# MCP1726_PINOUT.net
KiCad netlist of a schematic drawn in Altium Designer
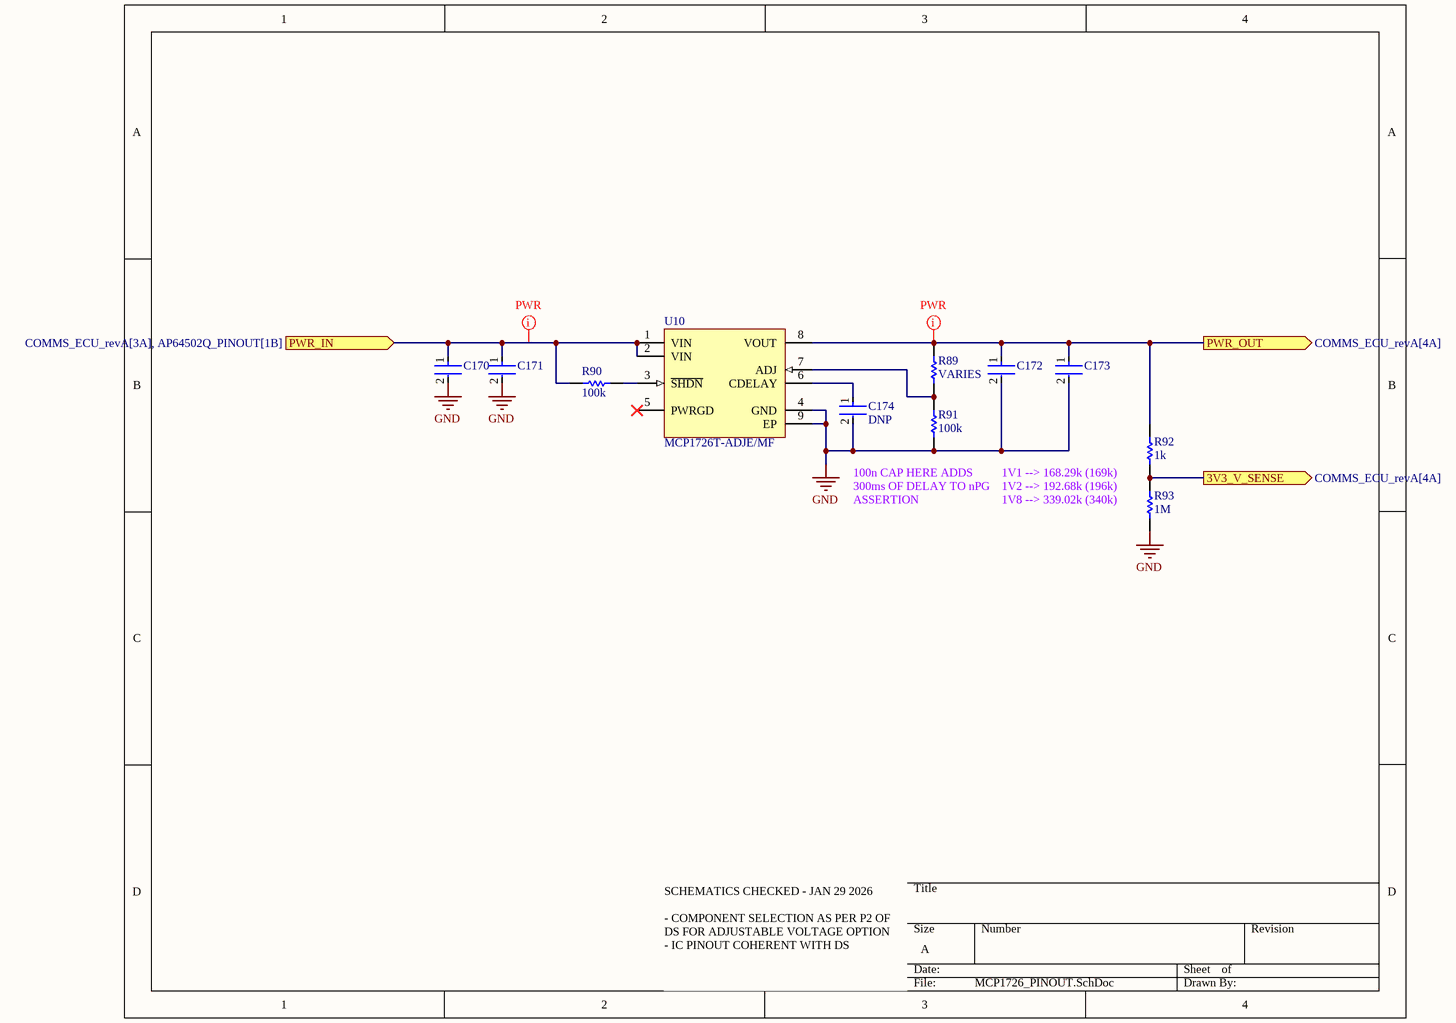
[diagram p0: MCP1726_PINOUT.SchDoc]

(export (version "E")
  (design (tool "Eeschema 10.0.6"))
  (components
    (comp (ref "C170")
      (value "C0805C475J4RACAUTO")
      (footprint "FP-C0805C475J4RACAUTO-MFG")
      (description "C0805C475J4RACAUTO Cap Ceramic 4.7uF 16V X7R 5% Pad SMD 0805 125C Automotive T/R")
      (fields (field (name "TOLERANCE") "5%"))
      (libsource (lib "Altium Content Vault") (part "b4654b650e69147ec39a6b967a45e02"))
    )
    (comp (ref "C171")
      (value "DNP")
      (footprint "FP-C0805C475J4RACAUTO-MFG")
      (description "C0805C475J4RACAUTO Cap Ceramic 4.7uF 16V X7R 5% Pad SMD 0805 125C Automotive T/R")
      (fields (field (name "TOLERANCE") "5%"))
      (libsource (lib "Altium Content Vault") (part "b4654b650e69147ec39a6b967a45e02"))
    )
    (comp (ref "C172")
      (value "HMK325B7105KN-T")
      (footprint "FP-1210-L_3_2_0_3-W_2_5_0-IPC_B")
      (description "None")
      (fields (field (name "TOLERANCE") "10%") (field (name "VOLTAGE") "100V"))
      (libsource (lib "Altium Content Vault") (part "02cd4be3c70576c341d710602a673aa"))
    )
    (comp (ref "C173")
      (value "DNP")
      (footprint "FP-1210-L_3_2_0_3-W_2_5_0-IPC_B")
      (description "None")
      (fields (field (name "TOLERANCE") "10%") (field (name "VOLTAGE") "100V"))
      (libsource (lib "Altium Content Vault") (part "02cd4be3c70576c341d710602a673aa"))
    )
    (comp (ref "C174")
      (value "DNP")
      (footprint "FP-0402-L_1_0_0_05-W_0_5-IPC_A")
      (description "LARGE PADS, 0402 CAP, CHANGE COMMENT TO MATCH REAL P/N")
      (libsource (lib "Space Concordia") (part "b4654b650e69147ec39a6b967a45e02"))
    )
    (comp (ref "R89")
      (value "VARIES")
      (footprint "R0603B")
      (description "Resistor")
      (libsource (lib "Space Concordia") (part "Resistor"))
    )
    (comp (ref "R90")
      (value "100k")
      (footprint "R0603B")
      (description "Resistor")
      (libsource (lib "Space Concordia") (part "Resistor"))
    )
    (comp (ref "R91")
      (value "100k")
      (footprint "R0603B")
      (description "Resistor")
      (libsource (lib "Space Concordia") (part "Resistor"))
    )
    (comp (ref "R92")
      (value "1k")
      (footprint "R0603B")
      (description "Resistor")
      (libsource (lib "Space Concordia") (part "Resistor"))
    )
    (comp (ref "R93")
      (value "1M")
      (footprint "R0603B")
      (description "Resistor")
      (libsource (lib "Space Concordia") (part "Resistor"))
    )
    (comp (ref "U10")
      (value "MCP1726T-ADJE/MF")
      (footprint "DFN-MF8")
      (libsource (lib "Altium Content Vault") (part "PM-LINEREG-MCP1726-IL9A"))
    )
  )
  (nets
    (net (code "1") (name "/3V3_V_SENSE") (class "Default")
      (node (ref "R92") (pin "1") (pinfunction "1_1") (pintype "passive"))
      (node (ref "R93") (pin "2") (pinfunction "2_2") (pintype "passive"))
    )
    (net (code "2") (name "/PWR_IN") (class "Default")
      (node (ref "C170") (pin "1") (pinfunction "1_1") (pintype "passive"))
      (node (ref "C171") (pin "1") (pinfunction "1_1") (pintype "passive"))
      (node (ref "R90") (pin "1") (pinfunction "1_1") (pintype "passive"))
      (node (ref "U10") (pin "1") (pinfunction "VIN_1") (pintype "power_in"))
      (node (ref "U10") (pin "2") (pinfunction "VIN_2") (pintype "power_in"))
    )
    (net (code "3") (name "/PWR_OUT") (class "Default")
      (node (ref "C172") (pin "1") (pinfunction "1_1") (pintype "passive"))
      (node (ref "C173") (pin "1") (pinfunction "1_1") (pintype "passive"))
      (node (ref "R89") (pin "2") (pinfunction "2_2") (pintype "passive"))
      (node (ref "R92") (pin "2") (pinfunction "2_2") (pintype "passive"))
      (node (ref "U10") (pin "8") (pinfunction "VOUT_8") (pintype "power_in"))
    )
    (net (code "4") (name "GND") (class "Default")
      (node (ref "C170") (pin "2") (pinfunction "2_2") (pintype "passive"))
      (node (ref "C171") (pin "2") (pinfunction "2_2") (pintype "passive"))
      (node (ref "C172") (pin "2") (pinfunction "2_2") (pintype "passive"))
      (node (ref "C173") (pin "2") (pinfunction "2_2") (pintype "passive"))
      (node (ref "C174") (pin "2") (pinfunction "2_2") (pintype "passive"))
      (node (ref "R91") (pin "1") (pinfunction "1_1") (pintype "passive"))
      (node (ref "R93") (pin "1") (pinfunction "1_1") (pintype "passive"))
      (node (ref "U10") (pin "4") (pinfunction "GND_4") (pintype "power_in"))
      (node (ref "U10") (pin "9") (pinfunction "EP_9") (pintype "power_in"))
    )
    (net (code "5") (name "Net-(U10-ADJ)") (class "Default")
      (node (ref "R89") (pin "1") (pinfunction "1_1") (pintype "passive"))
      (node (ref "R91") (pin "2") (pinfunction "2_2") (pintype "passive"))
      (node (ref "U10") (pin "7") (pinfunction "ADJ_7") (pintype "input"))
    )
    (net (code "6") (name "Net-(U10-CDELAY)") (class "Default")
      (node (ref "C174") (pin "1") (pinfunction "1_1") (pintype "passive"))
      (node (ref "U10") (pin "6") (pinfunction "CDELAY_6") (pintype "passive"))
    )
    (net (code "7") (name "Net-(U10-~{SHDN})") (class "Default")
      (node (ref "R90") (pin "2") (pinfunction "2_2") (pintype "passive"))
      (node (ref "U10") (pin "3") (pinfunction "~{SHDN}_3") (pintype "input"))
    )
    (net (code "8") (name "unconnected-(U10-PWRGD-Pad5)") (class "Default")
      (node (ref "U10") (pin "5") (pinfunction "PWRGD_5") (pintype "power_in+no_connect"))
    )
  )
)
